# schematics.net
KiCad netlist of a schematic drawn in EAGLE
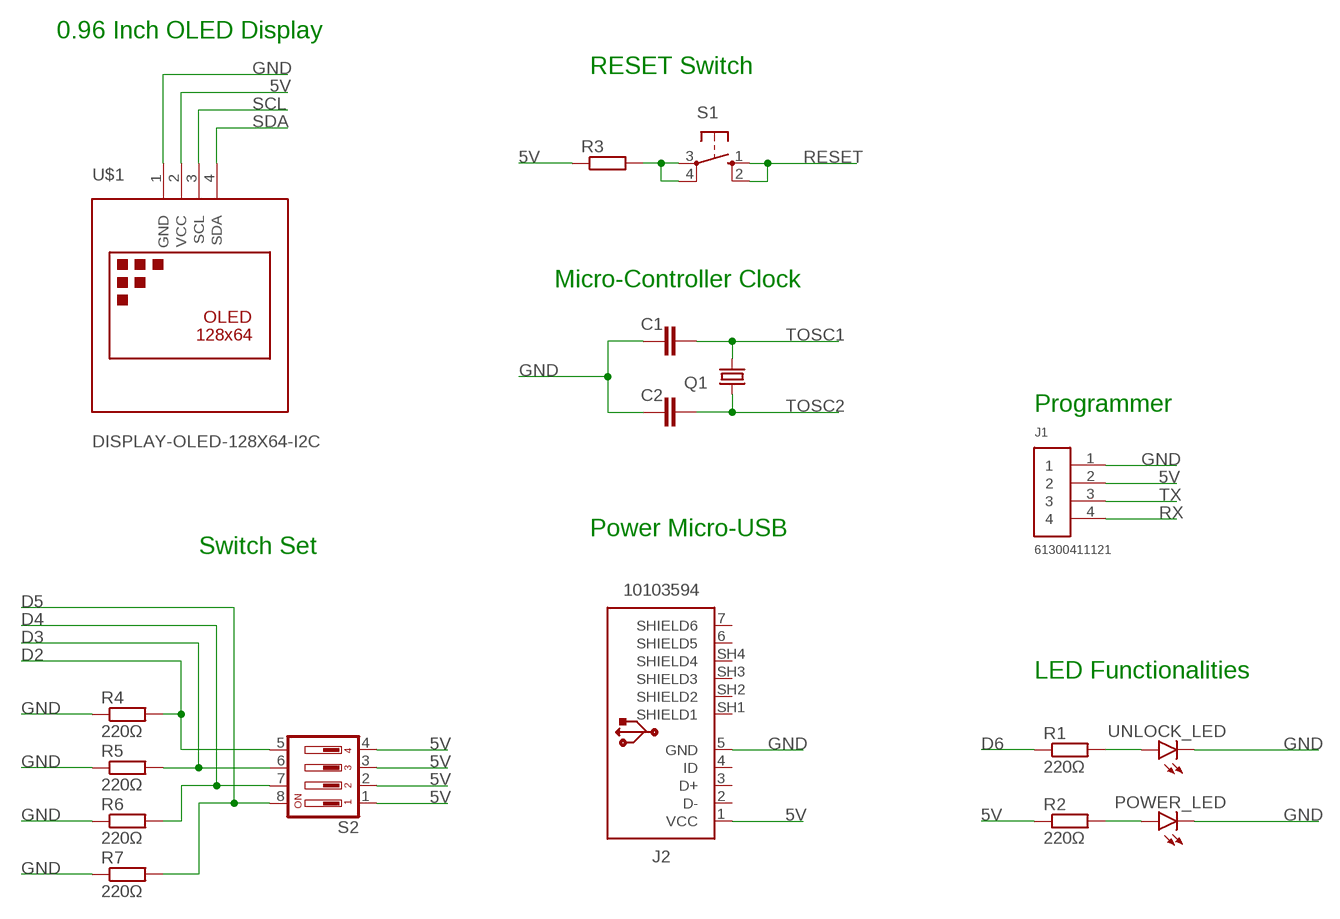
[diagram p0: schematic, sheet 1]

(export (version "E")
  (design (tool "Eeschema 10.0.6"))
  (components
    (comp (ref "C1")
      (value "C-EUC0805")
      (footprint "eagle-import:C0805")
      (libsource (lib "eagle-import") (part "C-EUC0805"))
    )
    (comp (ref "C2")
      (value "C-EUC0805")
      (footprint "eagle-import:C0805")
      (libsource (lib "eagle-import") (part "C-EUC0805"))
    )
    (comp (ref "J1")
      (value "61300411121")
      (footprint "eagle-import:61300411121")
      (fields
        (field (name "DIGI_KEY_PART_NUMBER") "732-5317-ND")
        (field (name "MANUFACTURER") "Wurth Electronics Inc.")
        (field (name "CREATED_BY") "PCBLayout.com")
      )
      (libsource (lib "eagle-import") (part "61300411121"))
    )
    (comp (ref "J2")
      (value "10103594")
      (footprint "eagle-import:10103594")
      (fields (field (name "MANUFACTURER") "Amphenol ICC (FCI)") (field (name "MPN") "10103594-0001LF"))
      (libsource (lib "eagle-import") (part "10103594"))
    )
    (comp (ref "POWER_LED")
      (value "LEDCHIP-LED0805")
      (footprint "eagle-import:CHIP-LED0805")
      (libsource (lib "eagle-import") (part "LEDCHIP-LED0805"))
    )
    (comp (ref "Q1")
      (value "CRYSTALHC49U-V")
      (footprint "eagle-import:HC49U-V")
      (libsource (lib "eagle-import") (part "CRYSTALHC49U-V"))
    )
    (comp (ref "R1")
      (value "220Ω")
      (footprint "eagle-import:R0805")
      (libsource (lib "eagle-import") (part "R-EU_R0805"))
    )
    (comp (ref "R2")
      (value "220Ω")
      (footprint "eagle-import:R0805")
      (libsource (lib "eagle-import") (part "R-EU_R0805"))
    )
    (comp (ref "R3")
      (value "R-EU_R0805")
      (footprint "eagle-import:R0805")
      (libsource (lib "eagle-import") (part "R-EU_R0805"))
    )
    (comp (ref "R4")
      (value "220Ω")
      (footprint "eagle-import:R0805")
      (libsource (lib "eagle-import") (part "R-EU_R0805"))
    )
    (comp (ref "R5")
      (value "220Ω")
      (footprint "eagle-import:R0805")
      (libsource (lib "eagle-import") (part "R-EU_R0805"))
    )
    (comp (ref "R6")
      (value "220Ω")
      (footprint "eagle-import:R0805")
      (libsource (lib "eagle-import") (part "R-EU_R0805"))
    )
    (comp (ref "R7")
      (value "220Ω")
      (footprint "eagle-import:R0805")
      (libsource (lib "eagle-import") (part "R-EU_R0805"))
    )
    (comp (ref "S1")
      (value "10-XX")
      (footprint "eagle-import:B3F-10XX")
      (fields (field (name "MPN") "B3F-1000"))
      (libsource (lib "eagle-import") (part "10-XX"))
    )
    (comp (ref "S2")
      (value "DA04")
      (footprint "eagle-import:DA-04")
      (fields (field (name "MPN") "MCDA04"))
      (libsource (lib "eagle-import") (part "DA04"))
    )
    (comp (ref "U$1")
      (value "DISPLAY-OLED-128X64-I2C")
      (footprint "eagle-import:DISPLAY-OLED-128X64-I2C")
      (libsource (lib "eagle-import") (part "DISPLAY-OLED-128X64-I2C"))
    )
    (comp (ref "UNLOCK_LED")
      (value "LEDCHIP-LED0805")
      (footprint "eagle-import:CHIP-LED0805")
      (libsource (lib "eagle-import") (part "LEDCHIP-LED0805"))
    )
  )
  (nets
    (net (code "1") (name "/5V") (class "Default")
      (node (ref "J1") (pin "2") (pinfunction "2_2") (pintype "passive"))
      (node (ref "J2") (pin "1") (pinfunction "VCC_1") (pintype "power_in"))
      (node (ref "R2") (pin "1") (pinfunction "1_1") (pintype "passive"))
      (node (ref "R3") (pin "1") (pinfunction "1_1") (pintype "passive"))
      (node (ref "S2") (pin "1") (pinfunction "1_1") (pintype "passive"))
      (node (ref "S2") (pin "2") (pinfunction "2_2") (pintype "passive"))
      (node (ref "S2") (pin "3") (pinfunction "3_3") (pintype "passive"))
      (node (ref "S2") (pin "4") (pinfunction "4_4") (pintype "passive"))
      (node (ref "U$1") (pin "2") (pinfunction "VCC_2") (pintype "power_in"))
    )
    (net (code "2") (name "/D2") (class "Default")
      (node (ref "R4") (pin "2") (pinfunction "2_2") (pintype "passive"))
      (node (ref "S2") (pin "5") (pinfunction "5_5") (pintype "passive"))
    )
    (net (code "3") (name "/D3") (class "Default")
      (node (ref "R5") (pin "2") (pinfunction "2_2") (pintype "passive"))
      (node (ref "S2") (pin "6") (pinfunction "6_6") (pintype "passive"))
    )
    (net (code "4") (name "/D4") (class "Default")
      (node (ref "R6") (pin "2") (pinfunction "2_2") (pintype "passive"))
      (node (ref "S2") (pin "7") (pinfunction "7_7") (pintype "passive"))
    )
    (net (code "5") (name "/D5") (class "Default")
      (node (ref "R7") (pin "2") (pinfunction "2_2") (pintype "passive"))
      (node (ref "S2") (pin "8") (pinfunction "8_8") (pintype "passive"))
    )
    (net (code "6") (name "/D6") (class "Default")
      (node (ref "R1") (pin "1") (pinfunction "1_1") (pintype "passive"))
    )
    (net (code "7") (name "/GND") (class "Default")
      (node (ref "C1") (pin "1") (pinfunction "1_1") (pintype "passive"))
      (node (ref "C2") (pin "1") (pinfunction "1_1") (pintype "passive"))
      (node (ref "J1") (pin "1") (pinfunction "1_1") (pintype "passive"))
      (node (ref "J2") (pin "5") (pinfunction "GND_5") (pintype "power_in"))
      (node (ref "POWER_LED") (pin "C") (pinfunction "C_C") (pintype "passive"))
      (node (ref "R4") (pin "1") (pinfunction "1_1") (pintype "passive"))
      (node (ref "R5") (pin "1") (pinfunction "1_1") (pintype "passive"))
      (node (ref "R6") (pin "1") (pinfunction "1_1") (pintype "passive"))
      (node (ref "R7") (pin "1") (pinfunction "1_1") (pintype "passive"))
      (node (ref "U$1") (pin "1") (pinfunction "GND_1") (pintype "power_in"))
      (node (ref "UNLOCK_LED") (pin "C") (pinfunction "C_C") (pintype "passive"))
    )
    (net (code "8") (name "/RESET") (class "Default")
      (node (ref "S1") (pin "1") (pinfunction "S_1") (pintype "passive"))
      (node (ref "S1") (pin "2") (pinfunction "S1_2") (pintype "passive"))
    )
    (net (code "9") (name "/RX") (class "Default")
      (node (ref "J1") (pin "4") (pinfunction "4_4") (pintype "passive"))
    )
    (net (code "10") (name "/SCL") (class "Default")
      (node (ref "U$1") (pin "3") (pinfunction "SCL_3") (pintype "bidirectional"))
    )
    (net (code "11") (name "/SDA") (class "Default")
      (node (ref "U$1") (pin "4") (pinfunction "SDA_4") (pintype "bidirectional"))
    )
    (net (code "12") (name "/SHIELD1") (class "Default")
      (node (ref "J2") (pin "SH1") (pinfunction "SHIELD1_SH1") (pintype "power_in"))
    )
    (net (code "13") (name "/SHIELD2") (class "Default")
      (node (ref "J2") (pin "SH2") (pinfunction "SHIELD2_SH2") (pintype "power_in"))
    )
    (net (code "14") (name "/SHIELD3") (class "Default")
      (node (ref "J2") (pin "SH3") (pinfunction "SHIELD3_SH3") (pintype "power_in"))
    )
    (net (code "15") (name "/SHIELD4") (class "Default")
      (node (ref "J2") (pin "SH4") (pinfunction "SHIELD4_SH4") (pintype "power_in"))
    )
    (net (code "16") (name "/SHIELD5") (class "Default")
      (node (ref "J2") (pin "6") (pinfunction "SHIELD5_6") (pintype "power_in"))
    )
    (net (code "17") (name "/SHIELD6") (class "Default")
      (node (ref "J2") (pin "7") (pinfunction "SHIELD6_7") (pintype "power_in"))
    )
    (net (code "18") (name "/TOSC1") (class "Default")
      (node (ref "C1") (pin "2") (pinfunction "2_2") (pintype "passive"))
      (node (ref "Q1") (pin "2") (pinfunction "2_2") (pintype "passive"))
    )
    (net (code "19") (name "/TOSC2") (class "Default")
      (node (ref "C2") (pin "2") (pinfunction "2_2") (pintype "passive"))
      (node (ref "Q1") (pin "1") (pinfunction "1_1") (pintype "passive"))
    )
    (net (code "20") (name "/TX") (class "Default")
      (node (ref "J1") (pin "3") (pinfunction "3_3") (pintype "passive"))
    )
    (net (code "21") (name "Net-(POWER_LED-PadA)") (class "Default")
      (node (ref "POWER_LED") (pin "A") (pinfunction "A_A") (pintype "passive"))
      (node (ref "R2") (pin "2") (pinfunction "2_2") (pintype "passive"))
    )
    (net (code "22") (name "Net-(R1-Pad2)") (class "Default")
      (node (ref "R1") (pin "2") (pinfunction "2_2") (pintype "passive"))
      (node (ref "UNLOCK_LED") (pin "A") (pinfunction "A_A") (pintype "passive"))
    )
    (net (code "23") (name "Net-(S1-P)") (class "Default")
      (node (ref "R3") (pin "2") (pinfunction "2_2") (pintype "passive"))
      (node (ref "S1") (pin "3") (pinfunction "P_3") (pintype "passive"))
      (node (ref "S1") (pin "4") (pinfunction "P1_4") (pintype "passive"))
    )
    (net (code "24") (name "unconnected-(J2-D+-Pad3)") (class "Default")
      (node (ref "J2") (pin "3") (pinfunction "D+_3") (pintype "bidirectional"))
    )
    (net (code "25") (name "unconnected-(J2-D--Pad2)") (class "Default")
      (node (ref "J2") (pin "2") (pinfunction "D-_2") (pintype "bidirectional"))
    )
    (net (code "26") (name "unconnected-(J2-ID-Pad4)") (class "Default")
      (node (ref "J2") (pin "4") (pinfunction "ID_4") (pintype "bidirectional"))
    )
  )
)
